# soth-ext.net
KiCad netlist of a schematic drawn in EAGLE
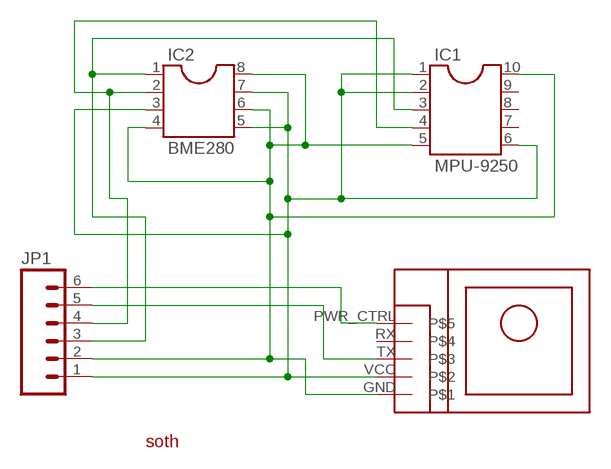
[diagram p0: schematic, sheet 1]

(export (version "E")
  (design (tool "Eeschema 10.0.6"))
  (components
    (comp (ref "IC1")
      (value "MPU-9250")
      (footprint "eagle-import:DIL10")
      (libsource (lib "eagle-import") (part "DIL10"))
    )
    (comp (ref "IC2")
      (value "BME280")
      (footprint "eagle-import:DIL08")
      (libsource (lib "eagle-import") (part "DIL8"))
    )
    (comp (ref "JP1")
      (value "M06SILK_FEMALE_PTH")
      (footprint "eagle-import:1X06")
      (libsource (lib "eagle-import") (part "M06SILK_FEMALE_PTH"))
    )
    (comp (ref "U$1")
      (value "GM318B")
      (footprint "eagle-import:GM318B")
      (libsource (lib "eagle-import") (part "GM318B"))
    )
    (comp (ref "U$2")
      (value "SOTH_LOGO")
      (footprint "eagle-import:SILK_LOGO")
      (libsource (lib "eagle-import") (part "SOTH_LOGO"))
    )
  )
  (nets
    (net (code "1") (name "Net-(IC1-Pad3)") (class "Default")
      (node (ref "IC1") (pin "3") (pinfunction "3_3") (pintype "passive"))
      (node (ref "IC2") (pin "1") (pinfunction "1_1") (pintype "passive"))
      (node (ref "JP1") (pin "3") (pinfunction "3_3") (pintype "passive"))
    )
    (net (code "2") (name "Net-(IC1-Pad4)") (class "Default")
      (node (ref "IC1") (pin "4") (pinfunction "4_4") (pintype "passive"))
      (node (ref "IC2") (pin "2") (pinfunction "2_2") (pintype "passive"))
      (node (ref "JP1") (pin "4") (pinfunction "4_4") (pintype "passive"))
    )
    (net (code "3") (name "Net-(U$1-P$1)") (class "Default")
      (node (ref "IC1") (pin "10") (pinfunction "10_10") (pintype "passive"))
      (node (ref "IC1") (pin "5") (pinfunction "5_5") (pintype "passive"))
      (node (ref "IC2") (pin "4") (pinfunction "4_4") (pintype "passive"))
      (node (ref "IC2") (pin "6") (pinfunction "6_6") (pintype "passive"))
      (node (ref "IC2") (pin "8") (pinfunction "8_8") (pintype "passive"))
      (node (ref "JP1") (pin "2") (pinfunction "2_2") (pintype "passive"))
      (node (ref "U$1") (pin "GND") (pinfunction "P$1_GND") (pintype "bidirectional"))
    )
    (net (code "4") (name "Net-(U$1-P$2)") (class "Default")
      (node (ref "IC1") (pin "1") (pinfunction "1_1") (pintype "passive"))
      (node (ref "IC1") (pin "2") (pinfunction "2_2") (pintype "passive"))
      (node (ref "IC1") (pin "6") (pinfunction "6_6") (pintype "passive"))
      (node (ref "IC2") (pin "3") (pinfunction "3_3") (pintype "passive"))
      (node (ref "IC2") (pin "5") (pinfunction "5_5") (pintype "passive"))
      (node (ref "IC2") (pin "7") (pinfunction "7_7") (pintype "passive"))
      (node (ref "JP1") (pin "1") (pinfunction "1_1") (pintype "passive"))
      (node (ref "U$1") (pin "VCC") (pinfunction "P$2_VCC") (pintype "bidirectional"))
    )
    (net (code "5") (name "Net-(U$1-P$3)") (class "Default")
      (node (ref "JP1") (pin "5") (pinfunction "5_5") (pintype "passive"))
      (node (ref "U$1") (pin "TX") (pinfunction "P$3_TX") (pintype "bidirectional"))
    )
    (net (code "6") (name "Net-(U$1-P$5)") (class "Default")
      (node (ref "JP1") (pin "6") (pinfunction "6_6") (pintype "passive"))
      (node (ref "U$1") (pin "PWR_CTRL") (pinfunction "P$5_PWR_CTRL") (pintype "bidirectional"))
    )
    (net (code "7") (name "unconnected-(IC1-Pad7)") (class "Default")
      (node (ref "IC1") (pin "7") (pinfunction "7_7") (pintype "passive"))
    )
    (net (code "8") (name "unconnected-(IC1-Pad8)") (class "Default")
      (node (ref "IC1") (pin "8") (pinfunction "8_8") (pintype "passive"))
    )
    (net (code "9") (name "unconnected-(IC1-Pad9)") (class "Default")
      (node (ref "IC1") (pin "9") (pinfunction "9_9") (pintype "passive"))
    )
    (net (code "10") (name "unconnected-(U$1-P$4-PadRX)") (class "Default")
      (node (ref "U$1") (pin "RX") (pinfunction "P$4_RX") (pintype "bidirectional"))
    )
  )
)
